# encoder.net
KiCad netlist of a schematic drawn in EAGLE
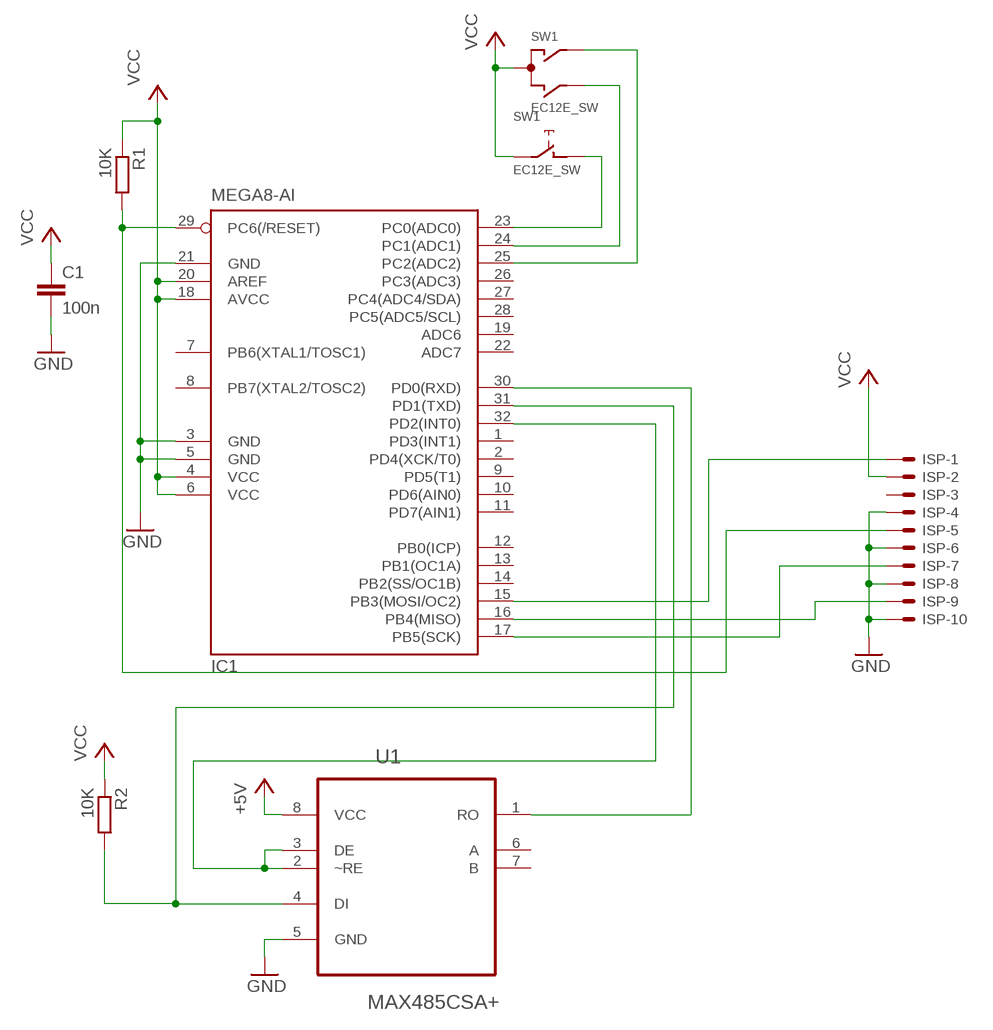
[diagram p0: schematic, sheet 1]

(export (version "E")
  (design (tool "Eeschema 10.0.6"))
  (components
    (comp (ref "C1")
      (value "100n")
      (footprint "eagle-import:C2.5-3")
      (libsource (lib "eagle-import") (part "C2,5-3"))
    )
    (comp (ref "IC1")
      (value "MEGA8-AI")
      (footprint "eagle-import:TQFP32-08")
      (fields (field (name "MPN") "ATMEGA8-16AU"))
      (libsource (lib "eagle-import") (part "MEGA8-AI"))
    )
    (comp (ref "ISP")
      (value "5566-10")
      (footprint "eagle-import:5566-10")
      (libsource (lib "eagle-import") (part "5566-10"))
    )
    (comp (ref "R1")
      (value "10K")
      (footprint "eagle-import:M1206")
      (libsource (lib "eagle-import") (part "R-EU_M1206"))
    )
    (comp (ref "R2")
      (value "10K")
      (footprint "eagle-import:M1206")
      (libsource (lib "eagle-import") (part "R-EU_M1206"))
    )
    (comp (ref "SW1")
      (value "EC12E_SW")
      (footprint "eagle-import:ALPS_EC12E_SW")
      (fields (field (name "MPN") "EC12E2424407"))
      (libsource (lib "eagle-import") (part "EC12E_SW"))
    )
    (comp (ref "U1")
      (value "MAX485CSA+")
      (footprint "eagle-import:SOIC127P600X175-8N")
      (libsource (lib "eagle-import") (part "MAX485CSA+"))
    )
  )
  (nets
    (net (code "1") (name "+5V") (class "Default")
      (node (ref "U1") (pin "8") (pinfunction "VCC_8") (pintype "power_in"))
    )
    (net (code "2") (name "GND") (class "Default")
      (node (ref "C1") (pin "2") (pinfunction "2_2") (pintype "passive"))
      (node (ref "IC1") (pin "21") (pinfunction "GND_21") (pintype "power_in"))
      (node (ref "IC1") (pin "3") (pinfunction "GND_3") (pintype "power_in"))
      (node (ref "IC1") (pin "5") (pinfunction "GND_5") (pintype "power_in"))
      (node (ref "ISP") (pin "10") (pinfunction "S_10") (pintype "passive"))
      (node (ref "ISP") (pin "4") (pinfunction "S_4") (pintype "passive"))
      (node (ref "ISP") (pin "6") (pinfunction "S_6") (pintype "passive"))
      (node (ref "ISP") (pin "8") (pinfunction "S_8") (pintype "passive"))
      (node (ref "U1") (pin "5") (pinfunction "GND_5") (pintype "passive"))
    )
    (net (code "3") (name "Net-(IC1-PB3(MOSI{slash}OC2))") (class "Default")
      (node (ref "IC1") (pin "15") (pinfunction "PB3(MOSI/OC2)_15") (pintype "bidirectional"))
      (node (ref "ISP") (pin "1") (pinfunction "S_1") (pintype "passive"))
    )
    (net (code "4") (name "Net-(IC1-PB4(MISO))") (class "Default")
      (node (ref "IC1") (pin "16") (pinfunction "PB4(MISO)_16") (pintype "bidirectional"))
      (node (ref "ISP") (pin "9") (pinfunction "S_9") (pintype "passive"))
    )
    (net (code "5") (name "Net-(IC1-PB5(SCK))") (class "Default")
      (node (ref "IC1") (pin "17") (pinfunction "PB5(SCK)_17") (pintype "bidirectional"))
      (node (ref "ISP") (pin "7") (pinfunction "S_7") (pintype "passive"))
    )
    (net (code "6") (name "Net-(IC1-PC0(ADC0))") (class "Default")
      (node (ref "IC1") (pin "23") (pinfunction "PC0(ADC0)_23") (pintype "bidirectional"))
      (node (ref "SW1") (pin "D") (pinfunction "1_D") (pintype "passive"))
    )
    (net (code "7") (name "Net-(IC1-PC1(ADC1))") (class "Default")
      (node (ref "IC1") (pin "24") (pinfunction "PC1(ADC1)_24") (pintype "bidirectional"))
      (node (ref "SW1") (pin "B") (pinfunction "B_B") (pintype "passive"))
    )
    (net (code "8") (name "Net-(IC1-PC2(ADC2))") (class "Default")
      (node (ref "IC1") (pin "25") (pinfunction "PC2(ADC2)_25") (pintype "bidirectional"))
      (node (ref "SW1") (pin "A") (pinfunction "A_A") (pintype "passive"))
    )
    (net (code "9") (name "Net-(IC1-PC6({slash}RESET))") (class "Default")
      (node (ref "IC1") (pin "29") (pinfunction "PC6(/RESET)_29") (pintype "bidirectional"))
      (node (ref "ISP") (pin "5") (pinfunction "S_5") (pintype "passive"))
      (node (ref "R1") (pin "2") (pinfunction "2_2") (pintype "passive"))
    )
    (net (code "10") (name "Net-(IC1-PD0(RXD))") (class "Default")
      (node (ref "IC1") (pin "30") (pinfunction "PD0(RXD)_30") (pintype "bidirectional"))
      (node (ref "U1") (pin "1") (pinfunction "RO_1") (pintype "output"))
    )
    (net (code "11") (name "Net-(IC1-PD1(TXD))") (class "Default")
      (node (ref "IC1") (pin "31") (pinfunction "PD1(TXD)_31") (pintype "bidirectional"))
      (node (ref "R2") (pin "2") (pinfunction "2_2") (pintype "passive"))
      (node (ref "U1") (pin "4") (pinfunction "DI_4") (pintype "input"))
    )
    (net (code "12") (name "Net-(IC1-PD2(INT0))") (class "Default")
      (node (ref "IC1") (pin "32") (pinfunction "PD2(INT0)_32") (pintype "bidirectional"))
      (node (ref "U1") (pin "2") (pinfunction "~{RE}_2") (pintype "input"))
      (node (ref "U1") (pin "3") (pinfunction "DE_3") (pintype "input"))
    )
    (net (code "13") (name "VCC") (class "Default")
      (node (ref "C1") (pin "1") (pinfunction "1_1") (pintype "passive"))
      (node (ref "IC1") (pin "18") (pinfunction "AVCC_18") (pintype "power_in"))
      (node (ref "IC1") (pin "20") (pinfunction "AREF_20") (pintype "passive"))
      (node (ref "IC1") (pin "4") (pinfunction "VCC_4") (pintype "power_in"))
      (node (ref "IC1") (pin "6") (pinfunction "VCC_6") (pintype "power_in"))
      (node (ref "ISP") (pin "2") (pinfunction "S_2") (pintype "passive"))
      (node (ref "R1") (pin "1") (pinfunction "1_1") (pintype "passive"))
      (node (ref "R2") (pin "1") (pinfunction "1_1") (pintype "passive"))
      (node (ref "SW1") (pin "C") (pinfunction "C_C") (pintype "passive"))
      (node (ref "SW1") (pin "E") (pinfunction "2_E") (pintype "passive"))
    )
    (net (code "14") (name "unconnected-(IC1-ADC6-Pad19)") (class "Default")
      (node (ref "IC1") (pin "19") (pinfunction "ADC6_19") (pintype "bidirectional"))
    )
    (net (code "15") (name "unconnected-(IC1-ADC7-Pad22)") (class "Default")
      (node (ref "IC1") (pin "22") (pinfunction "ADC7_22") (pintype "bidirectional"))
    )
    (net (code "16") (name "unconnected-(IC1-PB0(ICP)-Pad12)") (class "Default")
      (node (ref "IC1") (pin "12") (pinfunction "PB0(ICP)_12") (pintype "bidirectional"))
    )
    (net (code "17") (name "unconnected-(IC1-PB1(OC1A)-Pad13)") (class "Default")
      (node (ref "IC1") (pin "13") (pinfunction "PB1(OC1A)_13") (pintype "bidirectional"))
    )
    (net (code "18") (name "unconnected-(IC1-PB2(SS{slash}OC1B)-Pad14)") (class "Default")
      (node (ref "IC1") (pin "14") (pinfunction "PB2(SS/OC1B)_14") (pintype "bidirectional"))
    )
    (net (code "19") (name "unconnected-(IC1-PB6(XTAL1{slash}TOSC1)-Pad7)") (class "Default")
      (node (ref "IC1") (pin "7") (pinfunction "PB6(XTAL1/TOSC1)_7") (pintype "bidirectional"))
    )
    (net (code "20") (name "unconnected-(IC1-PB7(XTAL2{slash}TOSC2)-Pad8)") (class "Default")
      (node (ref "IC1") (pin "8") (pinfunction "PB7(XTAL2/TOSC2)_8") (pintype "bidirectional"))
    )
    (net (code "21") (name "unconnected-(IC1-PC3(ADC3)-Pad26)") (class "Default")
      (node (ref "IC1") (pin "26") (pinfunction "PC3(ADC3)_26") (pintype "bidirectional"))
    )
    (net (code "22") (name "unconnected-(IC1-PC4(ADC4{slash}SDA)-Pad27)") (class "Default")
      (node (ref "IC1") (pin "27") (pinfunction "PC4(ADC4/SDA)_27") (pintype "bidirectional"))
    )
    (net (code "23") (name "unconnected-(IC1-PC5(ADC5{slash}SCL)-Pad28)") (class "Default")
      (node (ref "IC1") (pin "28") (pinfunction "PC5(ADC5/SCL)_28") (pintype "bidirectional"))
    )
    (net (code "24") (name "unconnected-(IC1-PD3(INT1)-Pad1)") (class "Default")
      (node (ref "IC1") (pin "1") (pinfunction "PD3(INT1)_1") (pintype "bidirectional"))
    )
    (net (code "25") (name "unconnected-(IC1-PD4(XCK{slash}T0)-Pad2)") (class "Default")
      (node (ref "IC1") (pin "2") (pinfunction "PD4(XCK/T0)_2") (pintype "bidirectional"))
    )
    (net (code "26") (name "unconnected-(IC1-PD5(T1)-Pad9)") (class "Default")
      (node (ref "IC1") (pin "9") (pinfunction "PD5(T1)_9") (pintype "bidirectional"))
    )
    (net (code "27") (name "unconnected-(IC1-PD6(AIN0)-Pad10)") (class "Default")
      (node (ref "IC1") (pin "10") (pinfunction "PD6(AIN0)_10") (pintype "bidirectional"))
    )
    (net (code "28") (name "unconnected-(IC1-PD7(AIN1)-Pad11)") (class "Default")
      (node (ref "IC1") (pin "11") (pinfunction "PD7(AIN1)_11") (pintype "bidirectional"))
    )
    (net (code "29") (name "unconnected-(ISPD-S-Pad3)") (class "Default")
      (node (ref "ISP") (pin "3") (pinfunction "S_3") (pintype "passive"))
    )
    (net (code "30") (name "unconnected-(U1-A-Pad6)") (class "Default")
      (node (ref "U1") (pin "6") (pinfunction "A_6") (pintype "bidirectional"))
    )
    (net (code "31") (name "unconnected-(U1-B-Pad7)") (class "Default")
      (node (ref "U1") (pin "7") (pinfunction "B_7") (pintype "bidirectional"))
    )
  )
)
